# tinynano_ascii.net
KiCad netlist of a schematic drawn in Altium Designer
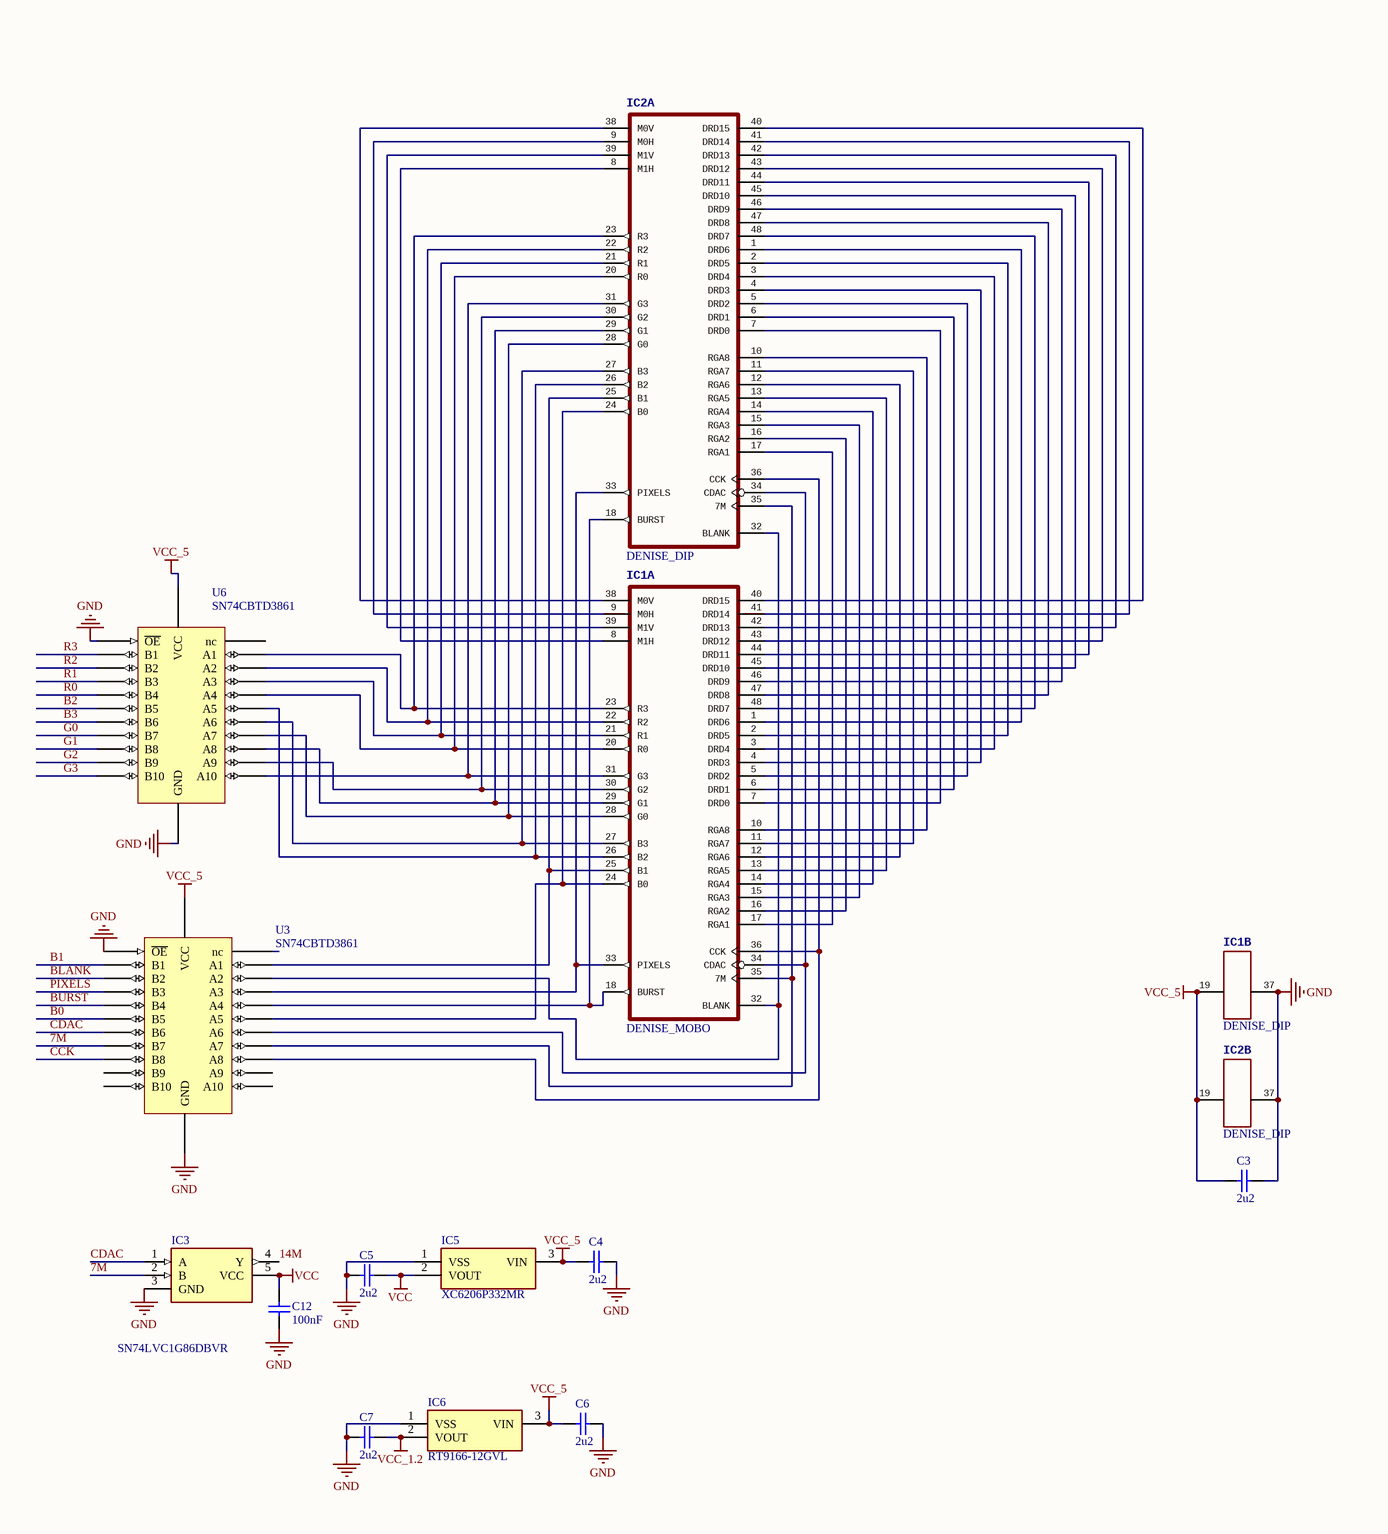
[diagram p0: tinynano_ascii.SchDoc, left]
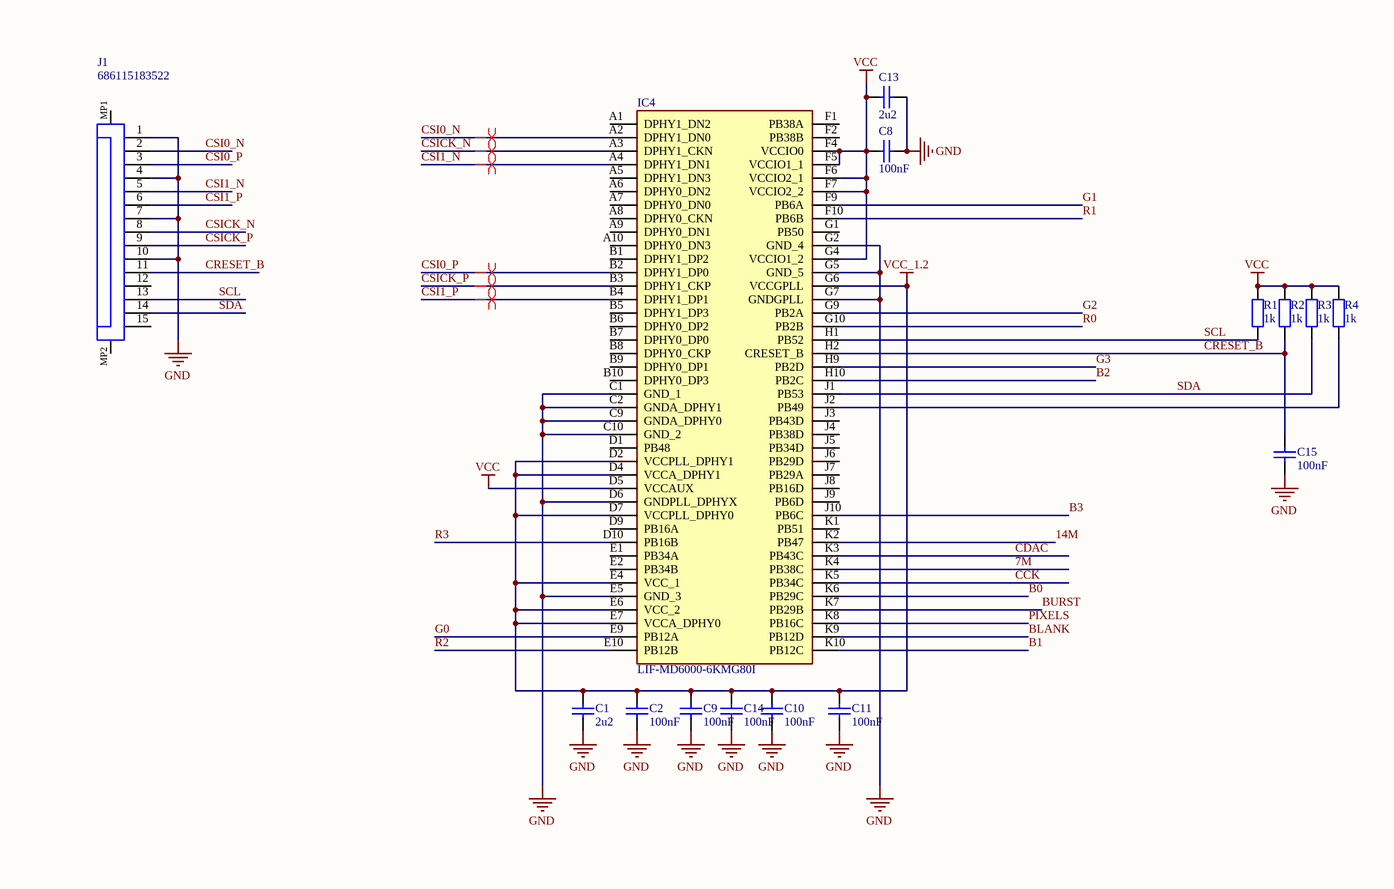
[diagram p1: tinynano_ascii.SchDoc, right]

(export (version "E")
  (design (tool "Eeschema 10.0.6"))
  (components
    (comp (ref "C1")
      (value "2u2")
      (footprint "1608[0603]")
      (description "Capacitor (Semiconductor SIM Model)")
      (fields (field (name "Comment") "Cap Semi") (field (name "PUBLISHER") "Altium Limited"))
      (libsource (lib "Miscellaneous Devices") (part "Cap Semi"))
    )
    (comp (ref "C2")
      (value "100nF")
      (footprint "0402")
      (description "Capacitor (Semiconductor SIM Model)")
      (fields (field (name "Comment") "Cap Semi") (field (name "PUBLISHER") "Altium Limited"))
      (libsource (lib "Miscellaneous Devices") (part "Cap Semi"))
    )
    (comp (ref "C3")
      (value "2u2")
      (footprint "1608[0603]")
      (description "Capacitor (Semiconductor SIM Model)")
      (fields (field (name "Comment") "Cap Semi") (field (name "PUBLISHER") "Altium Limited"))
      (libsource (lib "Miscellaneous Devices") (part "Cap Semi"))
    )
    (comp (ref "C4")
      (value "2u2")
      (footprint "1608[0603]")
      (description "Capacitor (Semiconductor SIM Model)")
      (fields (field (name "Comment") "Cap Semi") (field (name "PUBLISHER") "Altium Limited"))
      (libsource (lib "Miscellaneous Devices") (part "Cap Semi"))
    )
    (comp (ref "C5")
      (value "2u2")
      (footprint "1608[0603]")
      (description "Capacitor (Semiconductor SIM Model)")
      (fields (field (name "Comment") "Cap Semi") (field (name "PUBLISHER") "Altium Limited"))
      (libsource (lib "Miscellaneous Devices") (part "Cap Semi"))
    )
    (comp (ref "C6")
      (value "2u2")
      (footprint "1608[0603]")
      (description "Capacitor (Semiconductor SIM Model)")
      (fields (field (name "Comment") "Cap Semi") (field (name "PUBLISHER") "Altium Limited"))
      (libsource (lib "Miscellaneous Devices") (part "Cap Semi"))
    )
    (comp (ref "C7")
      (value "2u2")
      (footprint "1608[0603]")
      (description "Capacitor (Semiconductor SIM Model)")
      (fields (field (name "Comment") "Cap Semi") (field (name "PUBLISHER") "Altium Limited"))
      (libsource (lib "Miscellaneous Devices") (part "Cap Semi"))
    )
    (comp (ref "C8")
      (value "100nF")
      (footprint "0402")
      (description "Capacitor (Semiconductor SIM Model)")
      (fields (field (name "Comment") "Cap Semi") (field (name "PUBLISHER") "Altium Limited"))
      (libsource (lib "Miscellaneous Devices") (part "Cap Semi"))
    )
    (comp (ref "C9")
      (value "100nF")
      (footprint "0402")
      (description "Capacitor (Semiconductor SIM Model)")
      (fields (field (name "Comment") "Cap Semi") (field (name "PUBLISHER") "Altium Limited"))
      (libsource (lib "Miscellaneous Devices") (part "Cap Semi"))
    )
    (comp (ref "C10")
      (value "100nF")
      (footprint "0402")
      (description "Capacitor (Semiconductor SIM Model)")
      (fields (field (name "Comment") "Cap Semi") (field (name "PUBLISHER") "Altium Limited"))
      (libsource (lib "Miscellaneous Devices") (part "Cap Semi"))
    )
    (comp (ref "C11")
      (value "100nF")
      (footprint "0402")
      (description "Capacitor (Semiconductor SIM Model)")
      (fields (field (name "Comment") "Cap Semi") (field (name "PUBLISHER") "Altium Limited"))
      (libsource (lib "Miscellaneous Devices") (part "Cap Semi"))
    )
    (comp (ref "C12")
      (value "100nF")
      (footprint "0402")
      (description "Capacitor (Semiconductor SIM Model)")
      (fields (field (name "Comment") "Cap Semi") (field (name "PUBLISHER") "Altium Limited"))
      (libsource (lib "Miscellaneous Devices") (part "Cap Semi"))
    )
    (comp (ref "C13")
      (value "2u2")
      (footprint "1608[0603]")
      (description "Capacitor (Semiconductor SIM Model)")
      (fields (field (name "Comment") "Cap Semi") (field (name "PUBLISHER") "Altium Limited"))
      (libsource (lib "Miscellaneous Devices") (part "Cap Semi"))
    )
    (comp (ref "C14")
      (value "100nF")
      (footprint "1608[0603]")
      (description "Capacitor (Semiconductor SIM Model)")
      (fields (field (name "Comment") "Cap Semi") (field (name "PUBLISHER") "Altium Limited"))
      (libsource (lib "Miscellaneous Devices") (part "Cap Semi"))
    )
    (comp (ref "C15")
      (value "100nF")
      (footprint "0402")
      (description "Capacitor (Semiconductor SIM Model)")
      (fields (field (name "Comment") "Cap Semi") (field (name "PUBLISHER") "Altium Limited"))
      (libsource (lib "Miscellaneous Devices") (part "Cap Semi"))
    )
    (comp (ref "IC1")
      (value "DENISE_MOBO")
      (footprint "DIP48-6")
      (libsource (lib "Amiga") (part "DENISE_DIP"))
    )
    (comp (ref "IC2")
      (value "DENISE_DIP")
      (footprint "DIP48-6")
      (libsource (lib "Amiga") (part "DENISE_DIP"))
    )
    (comp (ref "IC3")
      (value "SN74LVC1G86DBVR")
      (footprint "SamacSys:SOT95P280X145-5N")
      (description "Integrated Circuit")
      (fields (field (name "MOUSER PART NUMBER") "595-SN74LVC1G86DBVR"))
      (libsource (lib "*") (part "SN74LVC1G86DBVR"))
    )
    (comp (ref "IC4")
      (value "LIF-MD6000-6KMG80I")
      (footprint "SamacSys:BGA80C65P10X10_700X700X120")
      (description "Integrated Circuit")
      (fields (field (name "MOUSER PART NUMBER") "842-LIFMD60006KMG80I"))
      (libsource (lib "*") (part "LIF-MD6000-6KMG80I"))
    )
    (comp (ref "IC5")
      (value "XC6206P332MR")
      (footprint "SamacSys:SOT95P280X130-3N")
      (description "Integrated Circuit")
      (libsource (lib "*") (part "XC6206P332MR"))
    )
    (comp (ref "IC6")
      (value "RT9166-12GVL")
      (footprint "SamacSys:SOT95P280X130-3N")
      (description "Integrated Circuit")
      (fields (field (name "MANUFACTURER_PART_NUMBER") "XC6206P332MR"))
      (libsource (lib "*") (part "XC6206P332MR"))
    )
    (comp (ref "J1")
      (value "686115183522")
      (footprint "686115183522")
      (description "WR-FPC SMT ZIF Horizontal Bottom Contact Low Profile, pitch 1mm, 15p")
      (fields (field (name "MANUFACTURER") "Wurth Elektronik"))
      (libsource (lib "Altium_WR-FPC (rev21a)") (part "686115183522"))
    )
    (comp (ref "R1")
      (value "1k")
      (footprint "0402-A")
      (description "Resistor")
      (fields (field (name "Comment") "Res2") (field (name "PUBLISHER") "Altium Limited"))
      (libsource (lib "Miscellaneous Devices") (part "Res2"))
    )
    (comp (ref "R2")
      (value "1k")
      (footprint "0402-A")
      (description "Resistor")
      (fields (field (name "Comment") "Res2") (field (name "PUBLISHER") "Altium Limited"))
      (libsource (lib "Miscellaneous Devices") (part "Res2"))
    )
    (comp (ref "R3")
      (value "1k")
      (footprint "0402-A")
      (description "Resistor")
      (fields (field (name "Comment") "Res2") (field (name "PUBLISHER") "Altium Limited"))
      (libsource (lib "Miscellaneous Devices") (part "Res2"))
    )
    (comp (ref "R4")
      (value "1k")
      (footprint "0402-A")
      (description "Resistor")
      (fields (field (name "Comment") "Res2") (field (name "PUBLISHER") "Altium Limited"))
      (libsource (lib "Miscellaneous Devices") (part "Res2"))
    )
    (comp (ref "U3")
      (value "SN74CBTD3861")
      (footprint "DB024")
      (description "10-bit FET bus level shifting switch")
      (libsource (lib "7Robot") (part "SN74CBTD3861"))
    )
    (comp (ref "U6")
      (value "SN74CBTD3861")
      (footprint "DB024")
      (description "10-bit FET bus level shifting switch")
      (libsource (lib "7Robot") (part "SN74CBTD3861"))
    )
  )
  (nets
    (net (code "1") (name "/7M") (class "Default")
      (node (ref "IC3") (pin "2") (pinfunction "B_2") (pintype "input"))
      (node (ref "IC4") (pin "K4") (pinfunction "PB38C_K4") (pintype "passive"))
      (node (ref "U3") (pin "16") (pinfunction "B7_16") (pintype "bidirectional"))
    )
    (net (code "2") (name "/14M") (class "Default")
      (node (ref "IC3") (pin "4") (pinfunction "Y_4") (pintype "output"))
      (node (ref "IC4") (pin "K2") (pinfunction "PB47_K2") (pintype "passive"))
    )
    (net (code "3") (name "/B0") (class "Default")
      (node (ref "IC4") (pin "K6") (pinfunction "PB29C_K6") (pintype "passive"))
      (node (ref "U3") (pin "18") (pinfunction "B5_18") (pintype "bidirectional"))
    )
    (net (code "4") (name "/B1") (class "Default")
      (node (ref "IC4") (pin "K10") (pinfunction "PB12C_K10") (pintype "passive"))
      (node (ref "U3") (pin "22") (pinfunction "B1_22") (pintype "bidirectional"))
    )
    (net (code "5") (name "/B2") (class "Default")
      (node (ref "IC4") (pin "H10") (pinfunction "PB2C_H10") (pintype "passive"))
      (node (ref "U6") (pin "18") (pinfunction "B5_18") (pintype "bidirectional"))
    )
    (net (code "6") (name "/B3") (class "Default")
      (node (ref "IC4") (pin "J10") (pinfunction "PB6C_J10") (pintype "passive"))
      (node (ref "U6") (pin "17") (pinfunction "B6_17") (pintype "bidirectional"))
    )
    (net (code "7") (name "/BLANK") (class "Default")
      (node (ref "IC4") (pin "K9") (pinfunction "PB12D_K9") (pintype "passive"))
      (node (ref "U3") (pin "21") (pinfunction "B2_21") (pintype "bidirectional"))
    )
    (net (code "8") (name "/BURST") (class "Default")
      (node (ref "IC4") (pin "K7") (pinfunction "PB29B_K7") (pintype "passive"))
      (node (ref "U3") (pin "19") (pinfunction "B4_19") (pintype "bidirectional"))
    )
    (net (code "9") (name "/CCK") (class "Default")
      (node (ref "IC4") (pin "K5") (pinfunction "PB34C_K5") (pintype "passive"))
      (node (ref "U3") (pin "15") (pinfunction "B8_15") (pintype "bidirectional"))
    )
    (net (code "10") (name "/CDAC") (class "Default")
      (node (ref "IC3") (pin "1") (pinfunction "A_1") (pintype "input"))
      (node (ref "IC4") (pin "K3") (pinfunction "PB43C_K3") (pintype "passive"))
      (node (ref "U3") (pin "17") (pinfunction "B6_17") (pintype "bidirectional"))
    )
    (net (code "11") (name "/CRESET_B") (class "Default")
      (node (ref "C15") (pin "2") (pinfunction "2_2") (pintype "passive"))
      (node (ref "IC4") (pin "H2") (pinfunction "CRESET_B_H2") (pintype "passive"))
      (node (ref "J1") (pin "11") (pinfunction "11_11") (pintype "passive"))
      (node (ref "R2") (pin "2") (pinfunction "2_2") (pintype "passive"))
    )
    (net (code "12") (name "/CSI0_N") (class "Default")
      (node (ref "IC4") (pin "A2") (pinfunction "DPHY1_DN0_A2") (pintype "passive"))
      (node (ref "J1") (pin "2") (pinfunction "2_2") (pintype "passive"))
    )
    (net (code "13") (name "/CSI0_P") (class "Default")
      (node (ref "IC4") (pin "B2") (pinfunction "DPHY1_DP0_B2") (pintype "passive"))
      (node (ref "J1") (pin "3") (pinfunction "3_3") (pintype "passive"))
    )
    (net (code "14") (name "/CSI1_N") (class "Default")
      (node (ref "IC4") (pin "A4") (pinfunction "DPHY1_DN1_A4") (pintype "passive"))
      (node (ref "J1") (pin "5") (pinfunction "5_5") (pintype "passive"))
    )
    (net (code "15") (name "/CSI1_P") (class "Default")
      (node (ref "IC4") (pin "B4") (pinfunction "DPHY1_DP1_B4") (pintype "passive"))
      (node (ref "J1") (pin "6") (pinfunction "6_6") (pintype "passive"))
    )
    (net (code "16") (name "/CSICK_N") (class "Default")
      (node (ref "IC4") (pin "A3") (pinfunction "DPHY1_CKN_A3") (pintype "passive"))
      (node (ref "J1") (pin "8") (pinfunction "8_8") (pintype "passive"))
    )
    (net (code "17") (name "/CSICK_P") (class "Default")
      (node (ref "IC4") (pin "B3") (pinfunction "DPHY1_CKP_B3") (pintype "passive"))
      (node (ref "J1") (pin "9") (pinfunction "9_9") (pintype "passive"))
    )
    (net (code "18") (name "/G0") (class "Default")
      (node (ref "IC4") (pin "E9") (pinfunction "PB12A_E9") (pintype "passive"))
      (node (ref "U6") (pin "16") (pinfunction "B7_16") (pintype "bidirectional"))
    )
    (net (code "19") (name "/G1") (class "Default")
      (node (ref "IC4") (pin "F9") (pinfunction "PB6A_F9") (pintype "passive"))
      (node (ref "U6") (pin "15") (pinfunction "B8_15") (pintype "bidirectional"))
    )
    (net (code "20") (name "/G2") (class "Default")
      (node (ref "IC4") (pin "G9") (pinfunction "PB2A_G9") (pintype "passive"))
      (node (ref "U6") (pin "14") (pinfunction "B9_14") (pintype "bidirectional"))
    )
    (net (code "21") (name "/G3") (class "Default")
      (node (ref "IC4") (pin "H9") (pinfunction "PB2D_H9") (pintype "passive"))
      (node (ref "U6") (pin "13") (pinfunction "B10_13") (pintype "bidirectional"))
    )
    (net (code "22") (name "/PIXELS") (class "Default")
      (node (ref "IC4") (pin "K8") (pinfunction "PB16C_K8") (pintype "passive"))
      (node (ref "U3") (pin "20") (pinfunction "B3_20") (pintype "bidirectional"))
    )
    (net (code "23") (name "/R0") (class "Default")
      (node (ref "IC4") (pin "G10") (pinfunction "PB2B_G10") (pintype "passive"))
      (node (ref "U6") (pin "19") (pinfunction "B4_19") (pintype "bidirectional"))
    )
    (net (code "24") (name "/R1") (class "Default")
      (node (ref "IC4") (pin "F10") (pinfunction "PB6B_F10") (pintype "passive"))
      (node (ref "U6") (pin "20") (pinfunction "B3_20") (pintype "bidirectional"))
    )
    (net (code "25") (name "/R2") (class "Default")
      (node (ref "IC4") (pin "E10") (pinfunction "PB12B_E10") (pintype "passive"))
      (node (ref "U6") (pin "21") (pinfunction "B2_21") (pintype "bidirectional"))
    )
    (net (code "26") (name "/R3") (class "Default")
      (node (ref "IC4") (pin "D10") (pinfunction "PB16B_D10") (pintype "passive"))
      (node (ref "U6") (pin "22") (pinfunction "B1_22") (pintype "bidirectional"))
    )
    (net (code "27") (name "/SCL") (class "Default")
      (node (ref "IC4") (pin "H1") (pinfunction "PB52_H1") (pintype "passive"))
      (node (ref "J1") (pin "13") (pinfunction "13_13") (pintype "passive"))
      (node (ref "R1") (pin "2") (pinfunction "2_2") (pintype "passive"))
    )
    (net (code "28") (name "/SDA") (class "Default")
      (node (ref "IC4") (pin "J1") (pinfunction "PB53_J1") (pintype "passive"))
      (node (ref "J1") (pin "14") (pinfunction "14_14") (pintype "passive"))
      (node (ref "R3") (pin "2") (pinfunction "2_2") (pintype "passive"))
    )
    (net (code "29") (name "GND") (class "Default")
      (node (ref "C1") (pin "2") (pinfunction "2_2") (pintype "passive"))
      (node (ref "C10") (pin "1") (pinfunction "1_1") (pintype "passive"))
      (node (ref "C11") (pin "1") (pinfunction "1_1") (pintype "passive"))
      (node (ref "C12") (pin "1") (pinfunction "1_1") (pintype "passive"))
      (node (ref "C13") (pin "2") (pinfunction "2_2") (pintype "passive"))
      (node (ref "C14") (pin "1") (pinfunction "1_1") (pintype "passive"))
      (node (ref "C15") (pin "1") (pinfunction "1_1") (pintype "passive"))
      (node (ref "C2") (pin "1") (pinfunction "1_1") (pintype "passive"))
      (node (ref "C3") (pin "1") (pinfunction "1_1") (pintype "passive"))
      (node (ref "C4") (pin "1") (pinfunction "1_1") (pintype "passive"))
      (node (ref "C5") (pin "2") (pinfunction "2_2") (pintype "passive"))
      (node (ref "C6") (pin "1") (pinfunction "1_1") (pintype "passive"))
      (node (ref "C7") (pin "2") (pinfunction "2_2") (pintype "passive"))
      (node (ref "C8") (pin "1") (pinfunction "1_1") (pintype "passive"))
      (node (ref "C9") (pin "1") (pinfunction "1_1") (pintype "passive"))
      (node (ref "IC1") (pin "37") (pinfunction "GND1_37") (pintype "power_in"))
      (node (ref "IC2") (pin "37") (pinfunction "GND1_37") (pintype "power_in"))
      (node (ref "IC3") (pin "3") (pinfunction "GND_3") (pintype "power_in"))
      (node (ref "IC4") (pin "C1") (pinfunction "GND_1_C1") (pintype "passive"))
      (node (ref "IC4") (pin "C10") (pinfunction "GND_2_C10") (pintype "passive"))
      (node (ref "IC4") (pin "C2") (pinfunction "GNDA_DPHY1_C2") (pintype "passive"))
      (node (ref "IC4") (pin "C9") (pinfunction "GNDA_DPHY0_C9") (pintype "passive"))
      (node (ref "IC4") (pin "D6") (pinfunction "GNDPLL_DPHYX_D6") (pintype "passive"))
      (node (ref "IC4") (pin "E5") (pinfunction "GND_3_E5") (pintype "passive"))
      (node (ref "IC4") (pin "G2") (pinfunction "GND_4_G2") (pintype "passive"))
      (node (ref "IC4") (pin "G5") (pinfunction "GND_5_G5") (pintype "passive"))
      (node (ref "IC4") (pin "G7") (pinfunction "GNDGPLL_G7") (pintype "passive"))
      (node (ref "IC5") (pin "1") (pinfunction "VSS_1") (pintype "passive"))
      (node (ref "IC6") (pin "1") (pinfunction "VSS_1") (pintype "passive"))
      (node (ref "J1") (pin "1") (pinfunction "1_1") (pintype "passive"))
      (node (ref "J1") (pin "10") (pinfunction "10_10") (pintype "passive"))
      (node (ref "J1") (pin "4") (pinfunction "4_4") (pintype "passive"))
      (node (ref "J1") (pin "7") (pinfunction "7_7") (pintype "passive"))
      (node (ref "U3") (pin "12") (pinfunction "GND_12") (pintype "power_in"))
      (node (ref "U3") (pin "23") (pinfunction "~{OE}_23") (pintype "input"))
      (node (ref "U6") (pin "12") (pinfunction "GND_12") (pintype "power_in"))
      (node (ref "U6") (pin "23") (pinfunction "~{OE}_23") (pintype "input"))
    )
    (net (code "30") (name "Net-(IC1A-7M)") (class "Default")
      (node (ref "IC1") (pin "35") (pinfunction "7M_35") (pintype "passive"))
      (node (ref "IC2") (pin "35") (pinfunction "7M_35") (pintype "passive"))
      (node (ref "U3") (pin "8") (pinfunction "A7_8") (pintype "bidirectional"))
    )
    (net (code "31") (name "Net-(IC1A-B0)") (class "Default")
      (node (ref "IC1") (pin "24") (pinfunction "B0_24") (pintype "output"))
      (node (ref "IC2") (pin "24") (pinfunction "B0_24") (pintype "output"))
      (node (ref "U3") (pin "6") (pinfunction "A5_6") (pintype "bidirectional"))
    )
    (net (code "32") (name "Net-(IC1A-B1)") (class "Default")
      (node (ref "IC1") (pin "25") (pinfunction "B1_25") (pintype "output"))
      (node (ref "IC2") (pin "25") (pinfunction "B1_25") (pintype "output"))
      (node (ref "U3") (pin "2") (pinfunction "A1_2") (pintype "bidirectional"))
    )
    (net (code "33") (name "Net-(IC1A-B2)") (class "Default")
      (node (ref "IC1") (pin "26") (pinfunction "B2_26") (pintype "output"))
      (node (ref "IC2") (pin "26") (pinfunction "B2_26") (pintype "output"))
      (node (ref "U6") (pin "6") (pinfunction "A5_6") (pintype "bidirectional"))
    )
    (net (code "34") (name "Net-(IC1A-B3)") (class "Default")
      (node (ref "IC1") (pin "27") (pinfunction "B3_27") (pintype "output"))
      (node (ref "IC2") (pin "27") (pinfunction "B3_27") (pintype "output"))
      (node (ref "U6") (pin "7") (pinfunction "A6_7") (pintype "bidirectional"))
    )
    (net (code "35") (name "Net-(IC1A-BLANK)") (class "Default")
      (node (ref "IC1") (pin "32") (pinfunction "BLANK_32") (pintype "passive"))
      (node (ref "IC2") (pin "32") (pinfunction "BLANK_32") (pintype "passive"))
      (node (ref "U3") (pin "3") (pinfunction "A2_3") (pintype "bidirectional"))
    )
    (net (code "36") (name "Net-(IC1A-BURST)") (class "Default")
      (node (ref "IC1") (pin "18") (pinfunction "BURST_18") (pintype "output"))
      (node (ref "IC2") (pin "18") (pinfunction "BURST_18") (pintype "output"))
      (node (ref "U3") (pin "5") (pinfunction "A4_5") (pintype "bidirectional"))
    )
    (net (code "37") (name "Net-(IC1A-CCK)") (class "Default")
      (node (ref "IC1") (pin "36") (pinfunction "CCK_36") (pintype "passive"))
      (node (ref "IC2") (pin "36") (pinfunction "CCK_36") (pintype "passive"))
      (node (ref "U3") (pin "9") (pinfunction "A8_9") (pintype "bidirectional"))
    )
    (net (code "38") (name "Net-(IC1A-CDAC)") (class "Default")
      (node (ref "IC1") (pin "34") (pinfunction "CDAC_34") (pintype "passive"))
      (node (ref "IC2") (pin "34") (pinfunction "CDAC_34") (pintype "passive"))
      (node (ref "U3") (pin "7") (pinfunction "A6_7") (pintype "bidirectional"))
    )
    (net (code "39") (name "Net-(IC1A-DRD0)") (class "Default")
      (node (ref "IC1") (pin "7") (pinfunction "DRD0_7") (pintype "passive"))
      (node (ref "IC2") (pin "7") (pinfunction "DRD0_7") (pintype "passive"))
    )
    (net (code "40") (name "Net-(IC1A-DRD1)") (class "Default")
      (node (ref "IC1") (pin "6") (pinfunction "DRD1_6") (pintype "passive"))
      (node (ref "IC2") (pin "6") (pinfunction "DRD1_6") (pintype "passive"))
    )
    (net (code "41") (name "Net-(IC1A-DRD2)") (class "Default")
      (node (ref "IC1") (pin "5") (pinfunction "DRD2_5") (pintype "passive"))
      (node (ref "IC2") (pin "5") (pinfunction "DRD2_5") (pintype "passive"))
    )
    (net (code "42") (name "Net-(IC1A-DRD3)") (class "Default")
      (node (ref "IC1") (pin "4") (pinfunction "DRD3_4") (pintype "passive"))
      (node (ref "IC2") (pin "4") (pinfunction "DRD3_4") (pintype "passive"))
    )
    (net (code "43") (name "Net-(IC1A-DRD4)") (class "Default")
      (node (ref "IC1") (pin "3") (pinfunction "DRD4_3") (pintype "passive"))
      (node (ref "IC2") (pin "3") (pinfunction "DRD4_3") (pintype "passive"))
    )
    (net (code "44") (name "Net-(IC1A-DRD5)") (class "Default")
      (node (ref "IC1") (pin "2") (pinfunction "DRD5_2") (pintype "passive"))
      (node (ref "IC2") (pin "2") (pinfunction "DRD5_2") (pintype "passive"))
    )
    (net (code "45") (name "Net-(IC1A-DRD6)") (class "Default")
      (node (ref "IC1") (pin "1") (pinfunction "DRD6_1") (pintype "passive"))
      (node (ref "IC2") (pin "1") (pinfunction "DRD6_1") (pintype "passive"))
    )
    (net (code "46") (name "Net-(IC1A-DRD7)") (class "Default")
      (node (ref "IC1") (pin "48") (pinfunction "DRD7_48") (pintype "passive"))
      (node (ref "IC2") (pin "48") (pinfunction "DRD7_48") (pintype "passive"))
    )
    (net (code "47") (name "Net-(IC1A-DRD8)") (class "Default")
      (node (ref "IC1") (pin "47") (pinfunction "DRD8_47") (pintype "passive"))
      (node (ref "IC2") (pin "47") (pinfunction "DRD8_47") (pintype "passive"))
    )
    (net (code "48") (name "Net-(IC1A-DRD9)") (class "Default")
      (node (ref "IC1") (pin "46") (pinfunction "DRD9_46") (pintype "passive"))
      (node (ref "IC2") (pin "46") (pinfunction "DRD9_46") (pintype "passive"))
    )
    (net (code "49") (name "Net-(IC1A-DRD10)") (class "Default")
      (node (ref "IC1") (pin "45") (pinfunction "DRD10_45") (pintype "passive"))
      (node (ref "IC2") (pin "45") (pinfunction "DRD10_45") (pintype "passive"))
    )
    (net (code "50") (name "Net-(IC1A-DRD11)") (class "Default")
      (node (ref "IC1") (pin "44") (pinfunction "DRD11_44") (pintype "passive"))
      (node (ref "IC2") (pin "44") (pinfunction "DRD11_44") (pintype "passive"))
    )
    (net (code "51") (name "Net-(IC1A-DRD12)") (class "Default")
      (node (ref "IC1") (pin "43") (pinfunction "DRD12_43") (pintype "passive"))
      (node (ref "IC2") (pin "43") (pinfunction "DRD12_43") (pintype "passive"))
    )
    (net (code "52") (name "Net-(IC1A-DRD13)") (class "Default")
      (node (ref "IC1") (pin "42") (pinfunction "DRD13_42") (pintype "passive"))
      (node (ref "IC2") (pin "42") (pinfunction "DRD13_42") (pintype "passive"))
    )
    (net (code "53") (name "Net-(IC1A-DRD14)") (class "Default")
      (node (ref "IC1") (pin "41") (pinfunction "DRD14_41") (pintype "passive"))
      (node (ref "IC2") (pin "41") (pinfunction "DRD14_41") (pintype "passive"))
    )
    (net (code "54") (name "Net-(IC1A-DRD15)") (class "Default")
      (node (ref "IC1") (pin "40") (pinfunction "DRD15_40") (pintype "passive"))
      (node (ref "IC2") (pin "40") (pinfunction "DRD15_40") (pintype "passive"))
    )
    (net (code "55") (name "Net-(IC1A-G0)") (class "Default")
      (node (ref "IC1") (pin "28") (pinfunction "G0_28") (pintype "output"))
      (node (ref "IC2") (pin "28") (pinfunction "G0_28") (pintype "output"))
      (node (ref "U6") (pin "8") (pinfunction "A7_8") (pintype "bidirectional"))
    )
    (net (code "56") (name "Net-(IC1A-G1)") (class "Default")
      (node (ref "IC1") (pin "29") (pinfunction "G1_29") (pintype "output"))
      (node (ref "IC2") (pin "29") (pinfunction "G1_29") (pintype "output"))
      (node (ref "U6") (pin "9") (pinfunction "A8_9") (pintype "bidirectional"))
    )
    (net (code "57") (name "Net-(IC1A-G2)") (class "Default")
      (node (ref "IC1") (pin "30") (pinfunction "G2_30") (pintype "output"))
      (node (ref "IC2") (pin "30") (pinfunction "G2_30") (pintype "output"))
      (node (ref "U6") (pin "10") (pinfunction "A9_10") (pintype "bidirectional"))
    )
    (net (code "58") (name "Net-(IC1A-G3)") (class "Default")
      (node (ref "IC1") (pin "31") (pinfunction "G3_31") (pintype "output"))
      (node (ref "IC2") (pin "31") (pinfunction "G3_31") (pintype "output"))
      (node (ref "U6") (pin "11") (pinfunction "A10_11") (pintype "bidirectional"))
    )
    (net (code "59") (name "Net-(IC1A-M0H)") (class "Default")
      (node (ref "IC1") (pin "9") (pinfunction "M0H_9") (pintype "passive"))
      (node (ref "IC2") (pin "9") (pinfunction "M0H_9") (pintype "passive"))
    )
    (net (code "60") (name "Net-(IC1A-M0V)") (class "Default")
      (node (ref "IC1") (pin "38") (pinfunction "M0V_38") (pintype "passive"))
      (node (ref "IC2") (pin "38") (pinfunction "M0V_38") (pintype "passive"))
    )
    (net (code "61") (name "Net-(IC1A-M1H)") (class "Default")
      (node (ref "IC1") (pin "8") (pinfunction "M1H_8") (pintype "passive"))
      (node (ref "IC2") (pin "8") (pinfunction "M1H_8") (pintype "passive"))
    )
    (net (code "62") (name "Net-(IC1A-M1V)") (class "Default")
      (node (ref "IC1") (pin "39") (pinfunction "M1V_39") (pintype "passive"))
      (node (ref "IC2") (pin "39") (pinfunction "M1V_39") (pintype "passive"))
    )
    (net (code "63") (name "Net-(IC1A-PIXELS)") (class "Default")
      (node (ref "IC1") (pin "33") (pinfunction "PIXELS_33") (pintype "output"))
      (node (ref "IC2") (pin "33") (pinfunction "PIXELS_33") (pintype "output"))
      (node (ref "U3") (pin "4") (pinfunction "A3_4") (pintype "bidirectional"))
    )
    (net (code "64") (name "Net-(IC1A-R0)") (class "Default")
      (node (ref "IC1") (pin "20") (pinfunction "R0_20") (pintype "output"))
      (node (ref "IC2") (pin "20") (pinfunction "R0_20") (pintype "output"))
      (node (ref "U6") (pin "5") (pinfunction "A4_5") (pintype "bidirectional"))
    )
    (net (code "65") (name "Net-(IC1A-R1)") (class "Default")
      (node (ref "IC1") (pin "21") (pinfunction "R1_21") (pintype "output"))
      (node (ref "IC2") (pin "21") (pinfunction "R1_21") (pintype "output"))
      (node (ref "U6") (pin "4") (pinfunction "A3_4") (pintype "bidirectional"))
    )
    (net (code "66") (name "Net-(IC1A-R2)") (class "Default")
      (node (ref "IC1") (pin "22") (pinfunction "R2_22") (pintype "output"))
      (node (ref "IC2") (pin "22") (pinfunction "R2_22") (pintype "output"))
      (node (ref "U6") (pin "3") (pinfunction "A2_3") (pintype "bidirectional"))
    )
    (net (code "67") (name "Net-(IC1A-R3)") (class "Default")
      (node (ref "IC1") (pin "23") (pinfunction "R3_23") (pintype "output"))
      (node (ref "IC2") (pin "23") (pinfunction "R3_23") (pintype "output"))
      (node (ref "U6") (pin "2") (pinfunction "A1_2") (pintype "bidirectional"))
    )
    (net (code "68") (name "Net-(IC1A-RGA1)") (class "Default")
      (node (ref "IC1") (pin "17") (pinfunction "RGA1_17") (pintype "passive"))
      (node (ref "IC2") (pin "17") (pinfunction "RGA1_17") (pintype "passive"))
    )
    (net (code "69") (name "Net-(IC1A-RGA2)") (class "Default")
      (node (ref "IC1") (pin "16") (pinfunction "RGA2_16") (pintype "passive"))
      (node (ref "IC2") (pin "16") (pinfunction "RGA2_16") (pintype "passive"))
    )
    (net (code "70") (name "Net-(IC1A-RGA3)") (class "Default")
      (node (ref "IC1") (pin "15") (pinfunction "RGA3_15") (pintype "passive"))
      (node (ref "IC2") (pin "15") (pinfunction "RGA3_15") (pintype "passive"))
    )
    (net (code "71") (name "Net-(IC1A-RGA4)") (class "Default")
      (node (ref "IC1") (pin "14") (pinfunction "RGA4_14") (pintype "passive"))
      (node (ref "IC2") (pin "14") (pinfunction "RGA4_14") (pintype "passive"))
    )
    (net (code "72") (name "Net-(IC1A-RGA5)") (class "Default")
      (node (ref "IC1") (pin "13") (pinfunction "RGA5_13") (pintype "passive"))
      (node (ref "IC2") (pin "13") (pinfunction "RGA5_13") (pintype "passive"))
    )
    (net (code "73") (name "Net-(IC1A-RGA6)") (class "Default")
      (node (ref "IC1") (pin "12") (pinfunction "RGA6_12") (pintype "passive"))
      (node (ref "IC2") (pin "12") (pinfunction "RGA6_12") (pintype "passive"))
    )
    (net (code "74") (name "Net-(IC1A-RGA7)") (class "Default")
      (node (ref "IC1") (pin "11") (pinfunction "RGA7_11") (pintype "passive"))
      (node (ref "IC2") (pin "11") (pinfunction "RGA7_11") (pintype "passive"))
    )
    (net (code "75") (name "Net-(IC1A-RGA8)") (class "Default")
      (node (ref "IC1") (pin "10") (pinfunction "RGA8_10") (pintype "passive"))
      (node (ref "IC2") (pin "10") (pinfunction "RGA8_10") (pintype "passive"))
    )
    (net (code "76") (name "Net-(IC4-PB49)") (class "Default")
      (node (ref "IC4") (pin "J2") (pinfunction "PB49_J2") (pintype "passive"))
      (node (ref "R4") (pin "2") (pinfunction "2_2") (pintype "passive"))
    )
    (net (code "77") (name "VCC") (class "Default")
      (node (ref "C12") (pin "2") (pinfunction "2_2") (pintype "passive"))
      (node (ref "C13") (pin "1") (pinfunction "1_1") (pintype "passive"))
      (node (ref "C5") (pin "1") (pinfunction "1_1") (pintype "passive"))
      (node (ref "C8") (pin "2") (pinfunction "2_2") (pintype "passive"))
      (node (ref "IC3") (pin "5") (pinfunction "VCC_5") (pintype "power_in"))
      (node (ref "IC4") (pin "D5") (pinfunction "VCCAUX_D5") (pintype "passive"))
      (node (ref "IC4") (pin "F4") (pinfunction "VCCIO0_F4") (pintype "passive"))
      (node (ref "IC4") (pin "F5") (pinfunction "VCCIO1_1_F5") (pintype "passive"))
      (node (ref "IC4") (pin "F6") (pinfunction "VCCIO2_1_F6") (pintype "passive"))
      (node (ref "IC4") (pin "F7") (pinfunction "VCCIO2_2_F7") (pintype "passive"))
      (node (ref "IC4") (pin "G4") (pinfunction "VCCIO1_2_G4") (pintype "passive"))
      (node (ref "IC5") (pin "2") (pinfunction "VOUT_2") (pintype "passive"))
      (node (ref "R1") (pin "1") (pinfunction "1_1") (pintype "passive"))
      (node (ref "R2") (pin "1") (pinfunction "1_1") (pintype "passive"))
      (node (ref "R3") (pin "1") (pinfunction "1_1") (pintype "passive"))
      (node (ref "R4") (pin "1") (pinfunction "1_1") (pintype "passive"))
    )
    (net (code "78") (name "VCC_1.2") (class "Default")
      (node (ref "C1") (pin "1") (pinfunction "1_1") (pintype "passive"))
      (node (ref "C10") (pin "2") (pinfunction "2_2") (pintype "passive"))
      (node (ref "C11") (pin "2") (pinfunction "2_2") (pintype "passive"))
      (node (ref "C14") (pin "2") (pinfunction "2_2") (pintype "passive"))
      (node (ref "C2") (pin "2") (pinfunction "2_2") (pintype "passive"))
      (node (ref "C7") (pin "1") (pinfunction "1_1") (pintype "passive"))
      (node (ref "C9") (pin "2") (pinfunction "2_2") (pintype "passive"))
      (node (ref "IC4") (pin "D2") (pinfunction "VCCPLL_DPHY1_D2") (pintype "passive"))
      (node (ref "IC4") (pin "D4") (pinfunction "VCCA_DPHY1_D4") (pintype "passive"))
      (node (ref "IC4") (pin "D7") (pinfunction "VCCPLL_DPHY0_D7") (pintype "passive"))
      (node (ref "IC4") (pin "E4") (pinfunction "VCC_1_E4") (pintype "passive"))
      (node (ref "IC4") (pin "E6") (pinfunction "VCC_2_E6") (pintype "passive"))
      (node (ref "IC4") (pin "E7") (pinfunction "VCCA_DPHY0_E7") (pintype "passive"))
      (node (ref "IC4") (pin "G6") (pinfunction "VCCGPLL_G6") (pintype "passive"))
      (node (ref "IC6") (pin "2") (pinfunction "VOUT_2") (pintype "passive"))
    )
    (net (code "79") (name "VCC_5") (class "Default")
      (node (ref "C3") (pin "2") (pinfunction "2_2") (pintype "passive"))
      (node (ref "C4") (pin "2") (pinfunction "2_2") (pintype "passive"))
      (node (ref "C6") (pin "2") (pinfunction "2_2") (pintype "passive"))
      (node (ref "IC1") (pin "19") (pinfunction "VCC1_19") (pintype "power_in"))
      (node (ref "IC2") (pin "19") (pinfunction "VCC1_19") (pintype "power_in"))
      (node (ref "IC5") (pin "3") (pinfunction "VIN_3") (pintype "passive"))
      (node (ref "IC6") (pin "3") (pinfunction "VIN_3") (pintype "passive"))
      (node (ref "U3") (pin "24") (pinfunction "VCC_24") (pintype "power_in"))
      (node (ref "U6") (pin "24") (pinfunction "VCC_24") (pintype "power_in"))
    )
    (net (code "80") (name "unconnected-(IC4-DPHY0_CKN-PadA8)") (class "Default")
      (node (ref "IC4") (pin "A8") (pinfunction "DPHY0_CKN_A8") (pintype "passive"))
    )
    (net (code "81") (name "unconnected-(IC4-DPHY0_CKP-PadB8)") (class "Default")
      (node (ref "IC4") (pin "B8") (pinfunction "DPHY0_CKP_B8") (pintype "passive"))
    )
    (net (code "82") (name "unconnected-(IC4-DPHY0_DN0-PadA7)") (class "Default")
      (node (ref "IC4") (pin "A7") (pinfunction "DPHY0_DN0_A7") (pintype "passive"))
    )
    (net (code "83") (name "unconnected-(IC4-DPHY0_DN1-PadA9)") (class "Default")
      (node (ref "IC4") (pin "A9") (pinfunction "DPHY0_DN1_A9") (pintype "passive"))
    )
    (net (code "84") (name "unconnected-(IC4-DPHY0_DN2-PadA6)") (class "Default")
      (node (ref "IC4") (pin "A6") (pinfunction "DPHY0_DN2_A6") (pintype "passive"))
    )
    (net (code "85") (name "unconnected-(IC4-DPHY0_DN3-PadA10)") (class "Default")
      (node (ref "IC4") (pin "A10") (pinfunction "DPHY0_DN3_A10") (pintype "passive"))
    )
    (net (code "86") (name "unconnected-(IC4-DPHY0_DP0-PadB7)") (class "Default")
      (node (ref "IC4") (pin "B7") (pinfunction "DPHY0_DP0_B7") (pintype "passive"))
    )
    (net (code "87") (name "unconnected-(IC4-DPHY0_DP1-PadB9)") (class "Default")
      (node (ref "IC4") (pin "B9") (pinfunction "DPHY0_DP1_B9") (pintype "passive"))
    )
    (net (code "88") (name "unconnected-(IC4-DPHY0_DP2-PadB6)") (class "Default")
      (node (ref "IC4") (pin "B6") (pinfunction "DPHY0_DP2_B6") (pintype "passive"))
    )
    (net (code "89") (name "unconnected-(IC4-DPHY0_DP3-PadB10)") (class "Default")
      (node (ref "IC4") (pin "B10") (pinfunction "DPHY0_DP3_B10") (pintype "passive"))
    )
    (net (code "90") (name "unconnected-(IC4-DPHY1_DN2-PadA1)") (class "Default")
      (node (ref "IC4") (pin "A1") (pinfunction "DPHY1_DN2_A1") (pintype "passive"))
    )
    (net (code "91") (name "unconnected-(IC4-DPHY1_DN3-PadA5)") (class "Default")
      (node (ref "IC4") (pin "A5") (pinfunction "DPHY1_DN3_A5") (pintype "passive"))
    )
    (net (code "92") (name "unconnected-(IC4-DPHY1_DP2-PadB1)") (class "Default")
      (node (ref "IC4") (pin "B1") (pinfunction "DPHY1_DP2_B1") (pintype "passive"))
    )
    (net (code "93") (name "unconnected-(IC4-DPHY1_DP3-PadB5)") (class "Default")
      (node (ref "IC4") (pin "B5") (pinfunction "DPHY1_DP3_B5") (pintype "passive"))
    )
    (net (code "94") (name "unconnected-(IC4-PB6D-PadJ9)") (class "Default")
      (node (ref "IC4") (pin "J9") (pinfunction "PB6D_J9") (pintype "passive"))
    )
    (net (code "95") (name "unconnected-(IC4-PB16A-PadD9)") (class "Default")
      (node (ref "IC4") (pin "D9") (pinfunction "PB16A_D9") (pintype "passive"))
    )
    (net (code "96") (name "unconnected-(IC4-PB16D-PadJ8)") (class "Default")
      (node (ref "IC4") (pin "J8") (pinfunction "PB16D_J8") (pintype "passive"))
    )
    (net (code "97") (name "unconnected-(IC4-PB29A-PadJ7)") (class "Default")
      (node (ref "IC4") (pin "J7") (pinfunction "PB29A_J7") (pintype "passive"))
    )
    (net (code "98") (name "unconnected-(IC4-PB29D-PadJ6)") (class "Default")
      (node (ref "IC4") (pin "J6") (pinfunction "PB29D_J6") (pintype "passive"))
    )
    (net (code "99") (name "unconnected-(IC4-PB34A-PadE1)") (class "Default")
      (node (ref "IC4") (pin "E1") (pinfunction "PB34A_E1") (pintype "passive"))
    )
    (net (code "100") (name "unconnected-(IC4-PB34B-PadE2)") (class "Default")
      (node (ref "IC4") (pin "E2") (pinfunction "PB34B_E2") (pintype "passive"))
    )
    (net (code "101") (name "unconnected-(IC4-PB34D-PadJ5)") (class "Default")
      (node (ref "IC4") (pin "J5") (pinfunction "PB34D_J5") (pintype "passive"))
    )
    (net (code "102") (name "unconnected-(IC4-PB38A-PadF1)") (class "Default")
      (node (ref "IC4") (pin "F1") (pinfunction "PB38A_F1") (pintype "passive"))
    )
    (net (code "103") (name "unconnected-(IC4-PB38B-PadF2)") (class "Default")
      (node (ref "IC4") (pin "F2") (pinfunction "PB38B_F2") (pintype "passive"))
    )
    (net (code "104") (name "unconnected-(IC4-PB38D-PadJ4)") (class "Default")
      (node (ref "IC4") (pin "J4") (pinfunction "PB38D_J4") (pintype "passive"))
    )
    (net (code "105") (name "unconnected-(IC4-PB43D-PadJ3)") (class "Default")
      (node (ref "IC4") (pin "J3") (pinfunction "PB43D_J3") (pintype "passive"))
    )
    (net (code "106") (name "unconnected-(IC4-PB48-PadD1)") (class "Default")
      (node (ref "IC4") (pin "D1") (pinfunction "PB48_D1") (pintype "passive"))
    )
    (net (code "107") (name "unconnected-(IC4-PB50-PadG1)") (class "Default")
      (node (ref "IC4") (pin "G1") (pinfunction "PB50_G1") (pintype "passive"))
    )
    (net (code "108") (name "unconnected-(IC4-PB51-PadK1)") (class "Default")
      (node (ref "IC4") (pin "K1") (pinfunction "PB51_K1") (pintype "passive"))
    )
    (net (code "109") (name "unconnected-(J1-Pad12)") (class "Default")
      (node (ref "J1") (pin "12") (pinfunction "12_12") (pintype "passive"))
    )
    (net (code "110") (name "unconnected-(J1-Pad15)") (class "Default")
      (node (ref "J1") (pin "15") (pinfunction "15_15") (pintype "passive"))
    )
    (net (code "111") (name "unconnected-(J1-PadMP1)") (class "Default")
      (node (ref "J1") (pin "MP1") (pinfunction "MP1_MP1") (pintype "passive"))
    )
    (net (code "112") (name "unconnected-(J1-PadMP2)") (class "Default")
      (node (ref "J1") (pin "MP2") (pinfunction "MP2_MP2") (pintype "passive"))
    )
    (net (code "113") (name "unconnected-(U3-A9-Pad10)") (class "Default")
      (node (ref "U3") (pin "10") (pinfunction "A9_10") (pintype "bidirectional"))
    )
    (net (code "114") (name "unconnected-(U3-A10-Pad11)") (class "Default")
      (node (ref "U3") (pin "11") (pinfunction "A10_11") (pintype "bidirectional"))
    )
    (net (code "115") (name "unconnected-(U3-B9-Pad14)") (class "Default")
      (node (ref "U3") (pin "14") (pinfunction "B9_14") (pintype "bidirectional"))
    )
    (net (code "116") (name "unconnected-(U3-B10-Pad13)") (class "Default")
      (node (ref "U3") (pin "13") (pinfunction "B10_13") (pintype "bidirectional"))
    )
    (net (code "117") (name "unconnected-(U3-nc-Pad1)") (class "Default")
      (node (ref "U3") (pin "1") (pinfunction "nc_1") (pintype "passive"))
    )
    (net (code "118") (name "unconnected-(U6-nc-Pad1)") (class "Default")
      (node (ref "U6") (pin "1") (pinfunction "nc_1") (pintype "passive"))
    )
  )
)
